# HTTP_POST_RELAY.net
KiCad netlist of a schematic drawn in EAGLE
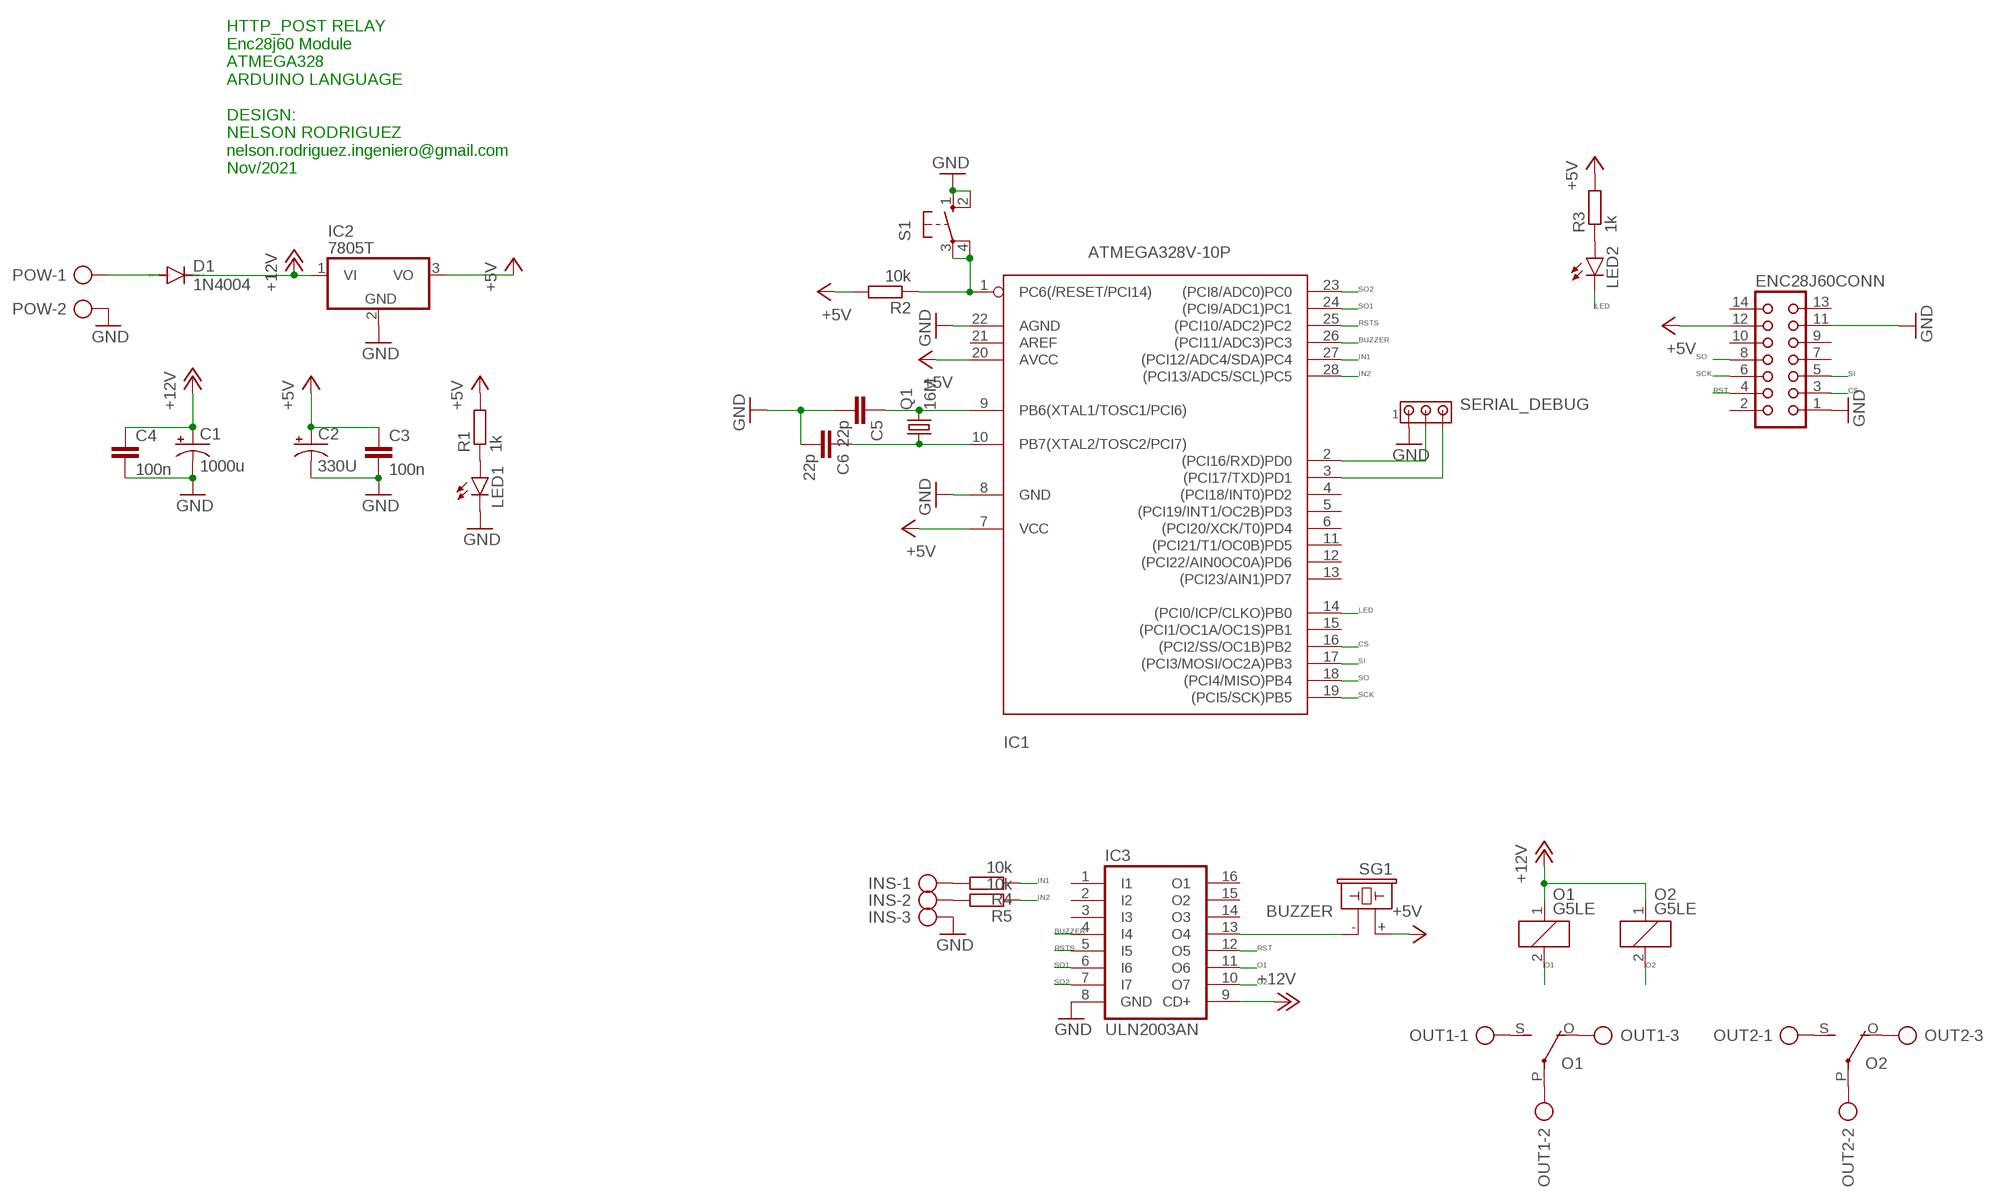
[diagram p0: schematic, sheet 1]

(export (version "E")
  (design (tool "Eeschema 10.0.6"))
  (components
    (comp (ref "C1")
      (value "1000u")
      (footprint "eagle-import:E2,5-6")
      (libsource (lib "eagle-import") (part "CPOL-USE2.5-6"))
    )
    (comp (ref "C2")
      (value "330U")
      (footprint "eagle-import:E2,5-6")
      (libsource (lib "eagle-import") (part "CPOL-USE2.5-6"))
    )
    (comp (ref "C3")
      (value "100n")
      (footprint "eagle-import:C025-024X044")
      (libsource (lib "eagle-import") (part "C-EU025-024X044"))
    )
    (comp (ref "C4")
      (value "100n")
      (footprint "eagle-import:C025-024X044")
      (libsource (lib "eagle-import") (part "C-EU025-024X044"))
    )
    (comp (ref "C5")
      (value "22p")
      (footprint "eagle-import:C025-024X044")
      (libsource (lib "eagle-import") (part "C-EU025-024X044"))
    )
    (comp (ref "C6")
      (value "22p")
      (footprint "eagle-import:C025-024X044")
      (libsource (lib "eagle-import") (part "C-EU025-024X044"))
    )
    (comp (ref "D1")
      (value "1N4004")
      (footprint "eagle-import:DO41-10")
      (libsource (lib "eagle-import") (part "1N4004"))
    )
    (comp (ref "ENC28J60CONN")
      (value "CON14")
      (footprint "eagle-import:CON14")
      (libsource (lib "eagle-import") (part "CON14"))
    )
    (comp (ref "IC1")
      (value "ATMEGA328V-10P")
      (footprint "eagle-import:DIL28-3")
      (libsource (lib "eagle-import") (part "ATMEGA328PV-10"))
    )
    (comp (ref "IC2")
      (value "7805T")
      (footprint "eagle-import:TO220H")
      (libsource (lib "eagle-import") (part "78T05"))
    )
    (comp (ref "IC3")
      (value "ULN2003AN")
      (footprint "eagle-import:DIL16")
      (libsource (lib "eagle-import") (part "ULN2003AN"))
    )
    (comp (ref "INS")
      (value "AK300/3")
      (footprint "eagle-import:AK300_3")
      (libsource (lib "eagle-import") (part "AK300/3"))
    )
    (comp (ref "LED1")
      (value "LED5MM")
      (footprint "eagle-import:LED5MM")
      (libsource (lib "eagle-import") (part "led_259_LED5MM"))
    )
    (comp (ref "LED2")
      (value "LED5MM")
      (footprint "eagle-import:LED5MM")
      (libsource (lib "eagle-import") (part "LED5MM"))
    )
    (comp (ref "O1")
      (value "G5LE")
      (footprint "eagle-import:G5LE")
      (libsource (lib "eagle-import") (part "G5LE"))
    )
    (comp (ref "O2")
      (value "G5LE")
      (footprint "eagle-import:G5LE")
      (libsource (lib "eagle-import") (part "G5LE"))
    )
    (comp (ref "OUT1")
      (value "AK300/3")
      (footprint "eagle-import:AK300_3")
      (libsource (lib "eagle-import") (part "AK300/3"))
    )
    (comp (ref "OUT2")
      (value "AK300/3")
      (footprint "eagle-import:AK300_3")
      (libsource (lib "eagle-import") (part "AK300/3"))
    )
    (comp (ref "POW")
      (value "AK300/2")
      (footprint "eagle-import:AK300_2")
      (libsource (lib "eagle-import") (part "AK300/2"))
    )
    (comp (ref "Q1")
      (value "16M")
      (footprint "eagle-import:HC49U-V")
      (libsource (lib "eagle-import") (part "CRYSTALHC49U-V"))
    )
    (comp (ref "R1")
      (value "1k")
      (footprint "eagle-import:0204_7")
      (libsource (lib "eagle-import") (part "R-EU_0204/7"))
    )
    (comp (ref "R2")
      (value "10k")
      (footprint "eagle-import:0204_7")
      (libsource (lib "eagle-import") (part "R-EU_0204/7"))
    )
    (comp (ref "R3")
      (value "1k")
      (footprint "eagle-import:0204_7")
      (libsource (lib "eagle-import") (part "R-EU_0204/7"))
    )
    (comp (ref "R4")
      (value "10k")
      (footprint "eagle-import:0204_7")
      (libsource (lib "eagle-import") (part "R-EU_0204/7"))
    )
    (comp (ref "R5")
      (value "10k")
      (footprint "eagle-import:0204_7")
      (libsource (lib "eagle-import") (part "R-EU_0204/7"))
    )
    (comp (ref "S1")
      (value "10-XX")
      (footprint "eagle-import:B3F-10XX")
      (fields (field (name "MPN") "B3F-1000"))
      (libsource (lib "eagle-import") (part "10-XX"))
    )
    (comp (ref "SERIAL_DEBUG")
      (value "MTA03-100")
      (footprint "eagle-import:10X03MTA")
      (libsource (lib "eagle-import") (part "MTA03-100"))
    )
    (comp (ref "SG1")
      (value "BUZZER")
      (footprint "eagle-import:F_CM12P")
      (libsource (lib "eagle-import") (part "F/CM12P"))
    )
  )
  (nets
    (net (code "1") (name "+5V") (class "Default")
      (node (ref "C2") (pin "+") (pinfunction "+_+") (pintype "passive"))
      (node (ref "C3") (pin "1") (pinfunction "1_1") (pintype "passive"))
      (node (ref "ENC28J60CONN") (pin "12") (pinfunction "12_12") (pintype "passive"))
      (node (ref "IC1") (pin "20") (pinfunction "AVCC_20") (pintype "bidirectional"))
      (node (ref "IC1") (pin "7") (pinfunction "VCC_7") (pintype "bidirectional"))
      (node (ref "IC2") (pin "3") (pinfunction "VO_3") (pintype "passive"))
      (node (ref "R1") (pin "2") (pinfunction "2_2") (pintype "passive"))
      (node (ref "R2") (pin "2") (pinfunction "2_2") (pintype "passive"))
      (node (ref "R3") (pin "2") (pinfunction "2_2") (pintype "passive"))
      (node (ref "SG1") (pin "+") (pinfunction "1_+") (pintype "passive"))
    )
    (net (code "2") (name "+12V") (class "Default")
      (node (ref "C1") (pin "+") (pinfunction "+_+") (pintype "passive"))
      (node (ref "C4") (pin "1") (pinfunction "1_1") (pintype "passive"))
      (node (ref "D1") (pin "C") (pinfunction "C_C") (pintype "passive"))
      (node (ref "IC2") (pin "1") (pinfunction "VI_1") (pintype "input"))
      (node (ref "IC3") (pin "9") (pinfunction "CD+_9") (pintype "passive"))
      (node (ref "O1") (pin "1") (pinfunction "1_1") (pintype "passive"))
      (node (ref "O2") (pin "1") (pinfunction "1_1") (pintype "passive"))
    )
    (net (code "3") (name "/BUZZER") (class "Default")
      (node (ref "IC1") (pin "26") (pinfunction "(PCI11/ADC3)PC3_26") (pintype "bidirectional"))
      (node (ref "IC3") (pin "4") (pinfunction "I4_4") (pintype "input"))
    )
    (net (code "4") (name "/CS") (class "Default")
      (node (ref "ENC28J60CONN") (pin "3") (pinfunction "3_3") (pintype "passive"))
      (node (ref "IC1") (pin "16") (pinfunction "(PCI2/SS/OC1B)PB2_16") (pintype "bidirectional"))
    )
    (net (code "5") (name "/IN1") (class "Default")
      (node (ref "IC1") (pin "27") (pinfunction "(PCI12/ADC4/SDA)PC4_27") (pintype "bidirectional"))
      (node (ref "R4") (pin "1") (pinfunction "1_1") (pintype "passive"))
    )
    (net (code "6") (name "/IN2") (class "Default")
      (node (ref "IC1") (pin "28") (pinfunction "(PCI13/ADC5/SCL)PC5_28") (pintype "bidirectional"))
      (node (ref "R5") (pin "1") (pinfunction "1_1") (pintype "passive"))
    )
    (net (code "7") (name "/LED") (class "Default")
      (node (ref "IC1") (pin "14") (pinfunction "(PCI0/ICP/CLKO)PB0_14") (pintype "bidirectional"))
      (node (ref "LED2") (pin "K") (pinfunction "C_K") (pintype "passive"))
    )
    (net (code "8") (name "/O1") (class "Default")
      (node (ref "IC3") (pin "11") (pinfunction "O6_11") (pintype "open_collector"))
      (node (ref "O1") (pin "2") (pinfunction "2_2") (pintype "passive"))
    )
    (net (code "9") (name "/O2") (class "Default")
      (node (ref "IC3") (pin "10") (pinfunction "O7_10") (pintype "open_collector"))
      (node (ref "O2") (pin "2") (pinfunction "2_2") (pintype "passive"))
    )
    (net (code "10") (name "/RST") (class "Default")
      (node (ref "ENC28J60CONN") (pin "4") (pinfunction "4_4") (pintype "passive"))
      (node (ref "IC3") (pin "12") (pinfunction "O5_12") (pintype "open_collector"))
    )
    (net (code "11") (name "/RSTS") (class "Default")
      (node (ref "IC1") (pin "25") (pinfunction "(PCI10/ADC2)PC2_25") (pintype "bidirectional"))
      (node (ref "IC3") (pin "5") (pinfunction "I5_5") (pintype "input"))
    )
    (net (code "12") (name "/SCK") (class "Default")
      (node (ref "ENC28J60CONN") (pin "6") (pinfunction "6_6") (pintype "passive"))
      (node (ref "IC1") (pin "19") (pinfunction "(PCI5/SCK)PB5_19") (pintype "bidirectional"))
    )
    (net (code "13") (name "/SI") (class "Default")
      (node (ref "ENC28J60CONN") (pin "5") (pinfunction "5_5") (pintype "passive"))
      (node (ref "IC1") (pin "17") (pinfunction "(PCI3/MOSI/OC2A)PB3_17") (pintype "bidirectional"))
    )
    (net (code "14") (name "/SO") (class "Default")
      (node (ref "ENC28J60CONN") (pin "8") (pinfunction "8_8") (pintype "passive"))
      (node (ref "IC1") (pin "18") (pinfunction "(PCI4/MISO)PB4_18") (pintype "bidirectional"))
    )
    (net (code "15") (name "/SO1") (class "Default")
      (node (ref "IC1") (pin "24") (pinfunction "(PCI9/ADC1)PC1_24") (pintype "bidirectional"))
      (node (ref "IC3") (pin "6") (pinfunction "I6_6") (pintype "input"))
    )
    (net (code "16") (name "/SO2") (class "Default")
      (node (ref "IC1") (pin "23") (pinfunction "(PCI8/ADC0)PC0_23") (pintype "bidirectional"))
      (node (ref "IC3") (pin "7") (pinfunction "I7_7") (pintype "input"))
    )
    (net (code "17") (name "GND") (class "Default")
      (node (ref "C1") (pin "-") (pinfunction "-_-") (pintype "passive"))
      (node (ref "C2") (pin "-") (pinfunction "-_-") (pintype "passive"))
      (node (ref "C3") (pin "2") (pinfunction "2_2") (pintype "passive"))
      (node (ref "C4") (pin "2") (pinfunction "2_2") (pintype "passive"))
      (node (ref "C5") (pin "2") (pinfunction "2_2") (pintype "passive"))
      (node (ref "C6") (pin "2") (pinfunction "2_2") (pintype "passive"))
      (node (ref "ENC28J60CONN") (pin "1") (pinfunction "1_1") (pintype "passive"))
      (node (ref "ENC28J60CONN") (pin "11") (pinfunction "11_11") (pintype "passive"))
      (node (ref "IC1") (pin "22") (pinfunction "AGND_22") (pintype "bidirectional"))
      (node (ref "IC1") (pin "8") (pinfunction "GND_8") (pintype "bidirectional"))
      (node (ref "IC2") (pin "2") (pinfunction "GND_2") (pintype "passive"))
      (node (ref "IC3") (pin "8") (pinfunction "GND_8") (pintype "power_in"))
      (node (ref "INS") (pin "3") (pinfunction "KL_3") (pintype "passive"))
      (node (ref "LED1") (pin "K") (pinfunction "C_K") (pintype "passive"))
      (node (ref "POW") (pin "2") (pinfunction "KL_2") (pintype "passive"))
      (node (ref "S1") (pin "1") (pinfunction "S_1") (pintype "passive"))
      (node (ref "S1") (pin "2") (pinfunction "S1_2") (pintype "passive"))
      (node (ref "SERIAL_DEBUG") (pin "1") (pinfunction "1_1") (pintype "passive"))
    )
    (net (code "18") (name "Net-(IC1-(PCI16{slash}RXD)PD0)") (class "Default")
      (node (ref "IC1") (pin "2") (pinfunction "(PCI16/RXD)PD0_2") (pintype "bidirectional"))
      (node (ref "SERIAL_DEBUG") (pin "2") (pinfunction "2_2") (pintype "passive"))
    )
    (net (code "19") (name "Net-(IC1-(PCI17{slash}TXD)PD1)") (class "Default")
      (node (ref "IC1") (pin "3") (pinfunction "(PCI17/TXD)PD1_3") (pintype "bidirectional"))
      (node (ref "SERIAL_DEBUG") (pin "3") (pinfunction "3_3") (pintype "passive"))
    )
    (net (code "20") (name "Net-(IC1-PB6(XTAL1{slash}TOSC1{slash}PCI6))") (class "Default")
      (node (ref "C5") (pin "1") (pinfunction "1_1") (pintype "passive"))
      (node (ref "IC1") (pin "9") (pinfunction "PB6(XTAL1/TOSC1/PCI6)_9") (pintype "bidirectional"))
      (node (ref "Q1") (pin "2") (pinfunction "2_2") (pintype "passive"))
    )
    (net (code "21") (name "Net-(IC1-PB7(XTAL2{slash}TOSC2{slash}PCI7))") (class "Default")
      (node (ref "C6") (pin "1") (pinfunction "1_1") (pintype "passive"))
      (node (ref "IC1") (pin "10") (pinfunction "PB7(XTAL2/TOSC2/PCI7)_10") (pintype "bidirectional"))
      (node (ref "Q1") (pin "1") (pinfunction "1_1") (pintype "passive"))
    )
    (net (code "22") (name "Net-(IC1-PC6({slash}RESET{slash}PCI14))") (class "Default")
      (node (ref "IC1") (pin "1") (pinfunction "PC6(/RESET/PCI14)_1") (pintype "bidirectional"))
      (node (ref "R2") (pin "1") (pinfunction "1_1") (pintype "passive"))
      (node (ref "S1") (pin "3") (pinfunction "P_3") (pintype "passive"))
      (node (ref "S1") (pin "4") (pinfunction "P1_4") (pintype "passive"))
    )
    (net (code "23") (name "Net-(IC3-O4)") (class "Default")
      (node (ref "IC3") (pin "13") (pinfunction "O4_13") (pintype "open_collector"))
      (node (ref "SG1") (pin "-") (pinfunction "2_-") (pintype "passive"))
    )
    (net (code "24") (name "Net-(INSA-KL)") (class "Default")
      (node (ref "INS") (pin "1") (pinfunction "KL_1") (pintype "passive"))
      (node (ref "R4") (pin "2") (pinfunction "2_2") (pintype "passive"))
    )
    (net (code "25") (name "Net-(INSB-KL)") (class "Default")
      (node (ref "INS") (pin "2") (pinfunction "KL_2") (pintype "passive"))
      (node (ref "R5") (pin "2") (pinfunction "2_2") (pintype "passive"))
    )
    (net (code "26") (name "Net-(LED1-PadA)") (class "Default")
      (node (ref "LED1") (pin "A") (pinfunction "A_A") (pintype "passive"))
      (node (ref "R1") (pin "1") (pinfunction "1_1") (pintype "passive"))
    )
    (net (code "27") (name "Net-(LED2-PadA)") (class "Default")
      (node (ref "LED2") (pin "A") (pinfunction "A_A") (pintype "passive"))
      (node (ref "R3") (pin "1") (pinfunction "1_1") (pintype "passive"))
    )
    (net (code "28") (name "Net-(OUT1A-KL)") (class "Default")
      (node (ref "O1") (pin "S") (pinfunction "S_S") (pintype "passive"))
      (node (ref "OUT1") (pin "1") (pinfunction "KL_1") (pintype "passive"))
    )
    (net (code "29") (name "Net-(OUT1B-KL)") (class "Default")
      (node (ref "O1") (pin "P") (pinfunction "P_P") (pintype "passive"))
      (node (ref "OUT1") (pin "2") (pinfunction "KL_2") (pintype "passive"))
    )
    (net (code "30") (name "Net-(OUT1C-KL)") (class "Default")
      (node (ref "O1") (pin "O") (pinfunction "O_O") (pintype "passive"))
      (node (ref "OUT1") (pin "3") (pinfunction "KL_3") (pintype "passive"))
    )
    (net (code "31") (name "Net-(OUT2A-KL)") (class "Default")
      (node (ref "O2") (pin "S") (pinfunction "S_S") (pintype "passive"))
      (node (ref "OUT2") (pin "1") (pinfunction "KL_1") (pintype "passive"))
    )
    (net (code "32") (name "Net-(OUT2B-KL)") (class "Default")
      (node (ref "O2") (pin "P") (pinfunction "P_P") (pintype "passive"))
      (node (ref "OUT2") (pin "2") (pinfunction "KL_2") (pintype "passive"))
    )
    (net (code "33") (name "Net-(OUT2C-KL)") (class "Default")
      (node (ref "O2") (pin "O") (pinfunction "O_O") (pintype "passive"))
      (node (ref "OUT2") (pin "3") (pinfunction "KL_3") (pintype "passive"))
    )
    (net (code "34") (name "Net-(POWA-KL)") (class "Default")
      (node (ref "D1") (pin "A") (pinfunction "A_A") (pintype "passive"))
      (node (ref "POW") (pin "1") (pinfunction "KL_1") (pintype "passive"))
    )
    (net (code "35") (name "unconnected-(ENC28J60CONN-Pad2)") (class "Default")
      (node (ref "ENC28J60CONN") (pin "2") (pinfunction "2_2") (pintype "passive"))
    )
    (net (code "36") (name "unconnected-(ENC28J60CONN-Pad7)") (class "Default")
      (node (ref "ENC28J60CONN") (pin "7") (pinfunction "7_7") (pintype "passive"))
    )
    (net (code "37") (name "unconnected-(ENC28J60CONN-Pad9)") (class "Default")
      (node (ref "ENC28J60CONN") (pin "9") (pinfunction "9_9") (pintype "passive"))
    )
    (net (code "38") (name "unconnected-(ENC28J60CONN-Pad10)") (class "Default")
      (node (ref "ENC28J60CONN") (pin "10") (pinfunction "10_10") (pintype "passive"))
    )
    (net (code "39") (name "unconnected-(ENC28J60CONN-Pad13)") (class "Default")
      (node (ref "ENC28J60CONN") (pin "13") (pinfunction "13_13") (pintype "passive"))
    )
    (net (code "40") (name "unconnected-(ENC28J60CONN-Pad14)") (class "Default")
      (node (ref "ENC28J60CONN") (pin "14") (pinfunction "14_14") (pintype "passive"))
    )
    (net (code "41") (name "unconnected-(IC1-(PCI1{slash}OC1A{slash}OC1S)PB1-Pad15)") (class "Default")
      (node (ref "IC1") (pin "15") (pinfunction "(PCI1/OC1A/OC1S)PB1_15") (pintype "bidirectional"))
    )
    (net (code "42") (name "unconnected-(IC1-(PCI18{slash}INT0)PD2-Pad4)") (class "Default")
      (node (ref "IC1") (pin "4") (pinfunction "(PCI18/INT0)PD2_4") (pintype "bidirectional"))
    )
    (net (code "43") (name "unconnected-(IC1-(PCI19{slash}INT1{slash}OC2B)PD3-Pad5)") (class "Default")
      (node (ref "IC1") (pin "5") (pinfunction "(PCI19/INT1/OC2B)PD3_5") (pintype "bidirectional"))
    )
    (net (code "44") (name "unconnected-(IC1-(PCI20{slash}XCK{slash}T0)PD4-Pad6)") (class "Default")
      (node (ref "IC1") (pin "6") (pinfunction "(PCI20/XCK/T0)PD4_6") (pintype "bidirectional"))
    )
    (net (code "45") (name "unconnected-(IC1-(PCI21{slash}T1{slash}OC0B)PD5-Pad11)") (class "Default")
      (node (ref "IC1") (pin "11") (pinfunction "(PCI21/T1/OC0B)PD5_11") (pintype "bidirectional"))
    )
    (net (code "46") (name "unconnected-(IC1-(PCI22{slash}AIN0OC0A)PD6-Pad12)") (class "Default")
      (node (ref "IC1") (pin "12") (pinfunction "(PCI22/AIN0OC0A)PD6_12") (pintype "bidirectional"))
    )
    (net (code "47") (name "unconnected-(IC1-(PCI23{slash}AIN1)PD7-Pad13)") (class "Default")
      (node (ref "IC1") (pin "13") (pinfunction "(PCI23/AIN1)PD7_13") (pintype "bidirectional"))
    )
    (net (code "48") (name "unconnected-(IC1-AREF-Pad21)") (class "Default")
      (node (ref "IC1") (pin "21") (pinfunction "AREF_21") (pintype "bidirectional"))
    )
    (net (code "49") (name "unconnected-(IC3-I1-Pad1)") (class "Default")
      (node (ref "IC3") (pin "1") (pinfunction "I1_1") (pintype "input"))
    )
    (net (code "50") (name "unconnected-(IC3-I2-Pad2)") (class "Default")
      (node (ref "IC3") (pin "2") (pinfunction "I2_2") (pintype "input"))
    )
    (net (code "51") (name "unconnected-(IC3-I3-Pad3)") (class "Default")
      (node (ref "IC3") (pin "3") (pinfunction "I3_3") (pintype "input"))
    )
    (net (code "52") (name "unconnected-(IC3-O1-Pad16)") (class "Default")
      (node (ref "IC3") (pin "16") (pinfunction "O1_16") (pintype "open_collector"))
    )
    (net (code "53") (name "unconnected-(IC3-O2-Pad15)") (class "Default")
      (node (ref "IC3") (pin "15") (pinfunction "O2_15") (pintype "open_collector"))
    )
    (net (code "54") (name "unconnected-(IC3-O3-Pad14)") (class "Default")
      (node (ref "IC3") (pin "14") (pinfunction "O3_14") (pintype "open_collector"))
    )
  )
)
